# tof.net
KiCad netlist of a schematic drawn in Altium Designer
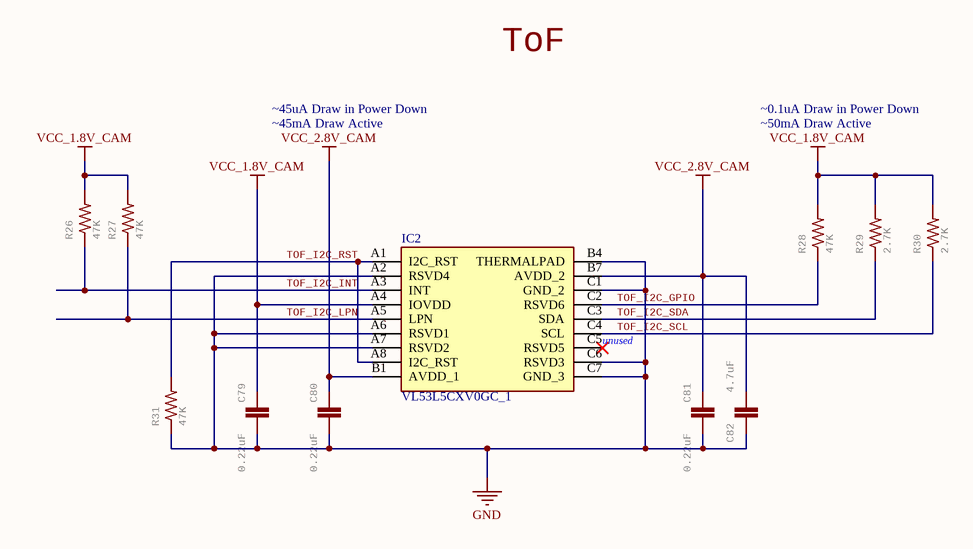
[diagram p0: tof.SchDoc]

(export (version "E")
  (design (tool "Eeschema 10.0.6"))
  (components
    (comp (ref "C79")
      (value "0.22uF")
      (footprint "C0201")
      (description "CAPACITOR, European symbol")
      (fields (field (name "MPN") "GRM033R60J224ME15D"))
      (libsource (lib "openmv-ae3") (part "C-EUC0201"))
    )
    (comp (ref "C80")
      (value "0.22uF")
      (footprint "C0201")
      (description "CAPACITOR, European symbol")
      (fields (field (name "MPN") "GRM033R60J224ME15D"))
      (libsource (lib "openmv-ae3") (part "C-EUC0201"))
    )
    (comp (ref "C81")
      (value "0.22uF")
      (footprint "C0201")
      (description "CAPACITOR, European symbol")
      (fields (field (name "MPN") "GRM033R60J224ME15D"))
      (libsource (lib "openmv-ae3") (part "C-EUC0201"))
    )
    (comp (ref "C82")
      (value "4.7uF")
      (footprint "0402-CAP")
      (description "0402 (1005 Metric) Nick Garner - TeleSense")
      (fields (field (name "MPN") "JMK105BBJ475MV-F"))
      (libsource (lib "openmv-ae3") (part "CAP_0402"))
    )
    (comp (ref "IC2")
      (value "VL53L5CXV0GC_1")
      (footprint "SamacSys:VL53L5CXV0GC1")
      (description "Integrated Circuit")
      (fields
        (field (name "MANUFACTURER_PART_NUMBER") "VL53L5CXV0GC/1")
        (field (name "MOUSER PART NUMBER") "511-VL53L5CXV0GC/1")
      )
      (libsource (lib "openmv-ae3") (part "VL53L5CXV0GC_1"))
    )
    (comp (ref "R26")
      (value "47K")
      (footprint "R0201")
      (fields (field (name "MPN") "RMCF0201FT47K0") (field (name "LIBRARYNAME") "sfe"))
      (libsource (lib "openmv-ae3") (part "RESISTOR0402-RES"))
    )
    (comp (ref "R27")
      (value "47K")
      (footprint "R0201")
      (fields (field (name "MPN") "RMCF0201FT47K0") (field (name "LIBRARYNAME") "sfe"))
      (libsource (lib "openmv-ae3") (part "RESISTOR0402-RES"))
    )
    (comp (ref "R28")
      (value "47K")
      (footprint "R0201")
      (fields (field (name "MPN") "RMCF0201FT47K0") (field (name "LIBRARYNAME") "sfe"))
      (libsource (lib "openmv-ae3") (part "RESISTOR0402-RES"))
    )
    (comp (ref "R29")
      (value "2.7K")
      (footprint "R0201")
      (fields (field (name "MPN") "RC0201JR-072K7L") (field (name "LIBRARYNAME") "sfe"))
      (libsource (lib "openmv-ae3") (part "RESISTOR0402-RES"))
    )
    (comp (ref "R30")
      (value "2.7K")
      (footprint "R0201")
      (fields (field (name "MPN") "RC0201JR-072K7L") (field (name "LIBRARYNAME") "sfe"))
      (libsource (lib "openmv-ae3") (part "RESISTOR0402-RES"))
    )
    (comp (ref "R31")
      (value "47K")
      (footprint "R0201")
      (fields (field (name "MPN") "RMCF0201FT47K0") (field (name "LIBRARYNAME") "sfe"))
      (libsource (lib "openmv-ae3") (part "RESISTOR0402-RES"))
    )
  )
  (nets
    (net (code "1") (name "/TOF_I2C_GPIO") (class "Default")
      (node (ref "IC2") (pin "C2") (pinfunction "RSVD6_C2") (pintype "passive"))
      (node (ref "R28") (pin "1") (pinfunction "1_1") (pintype "passive"))
    )
    (net (code "2") (name "/TOF_I2C_INT") (class "Default")
      (node (ref "IC2") (pin "A3") (pinfunction "INT_A3") (pintype "passive"))
      (node (ref "R26") (pin "1") (pinfunction "1_1") (pintype "passive"))
    )
    (net (code "3") (name "/TOF_I2C_LPN") (class "Default")
      (node (ref "IC2") (pin "A5") (pinfunction "LPN_A5") (pintype "passive"))
      (node (ref "R27") (pin "1") (pinfunction "1_1") (pintype "passive"))
    )
    (net (code "4") (name "/TOF_I2C_RST") (class "Default")
      (node (ref "IC2") (pin "A1") (pinfunction "I2C_RST_A1") (pintype "passive"))
      (node (ref "IC2") (pin "A8") (pinfunction "I2C_RST_A8") (pintype "passive"))
      (node (ref "R31") (pin "2") (pinfunction "2_2") (pintype "passive"))
    )
    (net (code "5") (name "/TOF_I2C_SCL") (class "Default")
      (node (ref "IC2") (pin "C4") (pinfunction "SCL_C4") (pintype "passive"))
      (node (ref "R30") (pin "1") (pinfunction "1_1") (pintype "passive"))
    )
    (net (code "6") (name "/TOF_I2C_SDA") (class "Default")
      (node (ref "IC2") (pin "C3") (pinfunction "SDA_C3") (pintype "passive"))
      (node (ref "R29") (pin "1") (pinfunction "1_1") (pintype "passive"))
    )
    (net (code "7") (name "GND") (class "Default")
      (node (ref "C79") (pin "2") (pinfunction "2_2") (pintype "passive"))
      (node (ref "C80") (pin "2") (pinfunction "2_2") (pintype "passive"))
      (node (ref "C81") (pin "2") (pinfunction "2_2") (pintype "passive"))
      (node (ref "C82") (pin "1") (pinfunction "1_1") (pintype "passive"))
      (node (ref "IC2") (pin "A2") (pinfunction "RSVD4_A2") (pintype "passive"))
      (node (ref "IC2") (pin "A6") (pinfunction "RSVD1_A6") (pintype "passive"))
      (node (ref "IC2") (pin "A7") (pinfunction "RSVD2_A7") (pintype "passive"))
      (node (ref "IC2") (pin "B4") (pinfunction "THERMALPAD_B4") (pintype "passive"))
      (node (ref "IC2") (pin "C1") (pinfunction "GND_2_C1") (pintype "passive"))
      (node (ref "IC2") (pin "C6") (pinfunction "RSVD3_C6") (pintype "passive"))
      (node (ref "IC2") (pin "C7") (pinfunction "GND_3_C7") (pintype "passive"))
      (node (ref "R31") (pin "1") (pinfunction "1_1") (pintype "passive"))
    )
    (net (code "8") (name "VCC_1.8V_CAM") (class "Default")
      (node (ref "C79") (pin "1") (pinfunction "1_1") (pintype "passive"))
      (node (ref "IC2") (pin "A4") (pinfunction "IOVDD_A4") (pintype "passive"))
      (node (ref "R26") (pin "2") (pinfunction "2_2") (pintype "passive"))
      (node (ref "R27") (pin "2") (pinfunction "2_2") (pintype "passive"))
      (node (ref "R28") (pin "2") (pinfunction "2_2") (pintype "passive"))
      (node (ref "R29") (pin "2") (pinfunction "2_2") (pintype "passive"))
      (node (ref "R30") (pin "2") (pinfunction "2_2") (pintype "passive"))
    )
    (net (code "9") (name "VCC_2.8V_CAM") (class "Default")
      (node (ref "C80") (pin "1") (pinfunction "1_1") (pintype "passive"))
      (node (ref "C81") (pin "1") (pinfunction "1_1") (pintype "passive"))
      (node (ref "C82") (pin "2") (pinfunction "2_2") (pintype "passive"))
      (node (ref "IC2") (pin "B1") (pinfunction "AVDD_1_B1") (pintype "passive"))
      (node (ref "IC2") (pin "B7") (pinfunction "AVDD_2_B7") (pintype "passive"))
    )
    (net (code "10") (name "unconnected-(IC2-RSVD5-PadC5)") (class "Default")
      (node (ref "IC2") (pin "C5") (pinfunction "RSVD5_C5") (pintype "passive+no_connect"))
    )
  )
)
